# Schematic.net
KiCad netlist of a schematic drawn in EAGLE
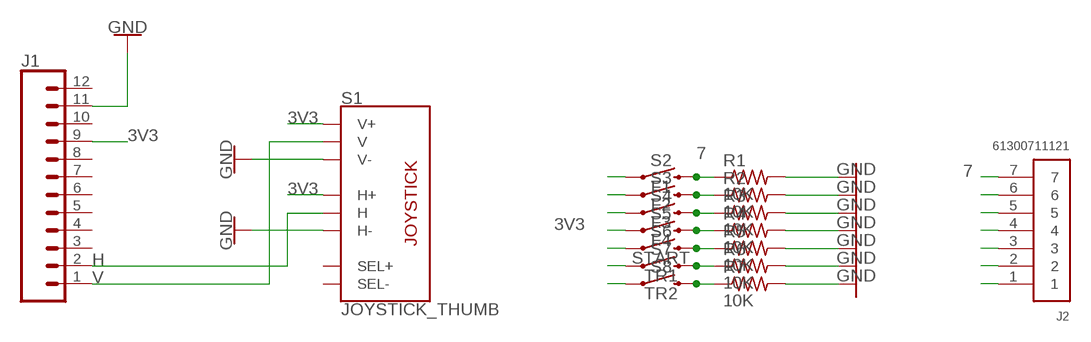
[diagram p0: schematic, sheet 1]

(export (version "E")
  (design (tool "Eeschema 10.0.6"))
  (components
    (comp (ref "J1")
      (value "CONN_12NO_SILK")
      (footprint "eagle-import:1X12_NO_SILK")
      (libsource (lib "eagle-import") (part "CONN_12NO_SILK"))
    )
    (comp (ref "J2")
      (value "61300711121")
      (footprint "eagle-import:61300711121")
      (fields
        (field (name "DIGI_KEY_PART_NUMBER") "732-5320-ND")
        (field (name "MANUFACTURER") "Wurth Electronics Inc.")
        (field (name "CREATED_BY") "PCBLayout.com")
      )
      (libsource (lib "eagle-import") (part "61300711121"))
    )
    (comp (ref "R1")
      (value "10K")
      (footprint "eagle-import:RES_1206")
      (fields
        (field (name "DIGIKEY_PART_NUMBER") "P0.0ETR-ND")
        (field (name "MANUFACTURER") "Panasonic Electronic Components")
        (field (name "MPN") "ERJ-8GEY0R00V")
        (field (name "CREATED_BY") "PCBLayout.com")
      )
      (libsource (lib "eagle-import") (part "ERJ-8GEY0R00V"))
    )
    (comp (ref "R2")
      (value "10K")
      (footprint "eagle-import:RES_1206")
      (fields
        (field (name "DIGIKEY_PART_NUMBER") "P0.0ETR-ND")
        (field (name "MANUFACTURER") "Panasonic Electronic Components")
        (field (name "MPN") "ERJ-8GEY0R00V")
        (field (name "CREATED_BY") "PCBLayout.com")
      )
      (libsource (lib "eagle-import") (part "ERJ-8GEY0R00V"))
    )
    (comp (ref "R3")
      (value "10K")
      (footprint "eagle-import:RES_1206")
      (fields
        (field (name "DIGIKEY_PART_NUMBER") "P0.0ETR-ND")
        (field (name "MANUFACTURER") "Panasonic Electronic Components")
        (field (name "MPN") "ERJ-8GEY0R00V")
        (field (name "CREATED_BY") "PCBLayout.com")
      )
      (libsource (lib "eagle-import") (part "ERJ-8GEY0R00V"))
    )
    (comp (ref "R4")
      (value "10K")
      (footprint "eagle-import:RES_1206")
      (fields
        (field (name "DIGIKEY_PART_NUMBER") "P0.0ETR-ND")
        (field (name "MANUFACTURER") "Panasonic Electronic Components")
        (field (name "MPN") "ERJ-8GEY0R00V")
        (field (name "CREATED_BY") "PCBLayout.com")
      )
      (libsource (lib "eagle-import") (part "ERJ-8GEY0R00V"))
    )
    (comp (ref "R5")
      (value "10K")
      (footprint "eagle-import:RES_1206")
      (fields
        (field (name "DIGIKEY_PART_NUMBER") "P0.0ETR-ND")
        (field (name "MANUFACTURER") "Panasonic Electronic Components")
        (field (name "MPN") "ERJ-8GEY0R00V")
        (field (name "CREATED_BY") "PCBLayout.com")
      )
      (libsource (lib "eagle-import") (part "ERJ-8GEY0R00V"))
    )
    (comp (ref "R6")
      (value "10K")
      (footprint "eagle-import:RES_1206")
      (fields
        (field (name "DIGIKEY_PART_NUMBER") "P0.0ETR-ND")
        (field (name "MANUFACTURER") "Panasonic Electronic Components")
        (field (name "MPN") "ERJ-8GEY0R00V")
        (field (name "CREATED_BY") "PCBLayout.com")
      )
      (libsource (lib "eagle-import") (part "ERJ-8GEY0R00V"))
    )
    (comp (ref "R7")
      (value "10K")
      (footprint "eagle-import:RES_1206")
      (fields
        (field (name "DIGIKEY_PART_NUMBER") "P0.0ETR-ND")
        (field (name "MANUFACTURER") "Panasonic Electronic Components")
        (field (name "MPN") "ERJ-8GEY0R00V")
        (field (name "CREATED_BY") "PCBLayout.com")
      )
      (libsource (lib "eagle-import") (part "ERJ-8GEY0R00V"))
    )
    (comp (ref "S1")
      (value "JOYSTICK_THUMB")
      (footprint "eagle-import:JOYSTICK")
      (libsource (lib "eagle-import") (part "JOYSTICK_THUMB"))
    )
    (comp (ref "S2")
      (value "F1")
      (footprint "eagle-import:TACTILE_SWITCH_PTH_12MM")
      (libsource (lib "eagle-import") (part "MOMENTARY-SWITCH-SPST-PTH-12MM"))
    )
    (comp (ref "S3")
      (value "F2")
      (footprint "eagle-import:TACTILE_SWITCH_PTH_12MM")
      (libsource (lib "eagle-import") (part "MOMENTARY-SWITCH-SPST-PTH-12MM"))
    )
    (comp (ref "S4")
      (value "F3")
      (footprint "eagle-import:TACTILE_SWITCH_PTH_12MM")
      (libsource (lib "eagle-import") (part "MOMENTARY-SWITCH-SPST-PTH-12MM"))
    )
    (comp (ref "S5")
      (value "F4")
      (footprint "eagle-import:TACTILE_SWITCH_PTH_12MM")
      (libsource (lib "eagle-import") (part "MOMENTARY-SWITCH-SPST-PTH-12MM"))
    )
    (comp (ref "S6")
      (value "START")
      (footprint "eagle-import:TACTILE_SWITCH_PTH_12MM")
      (libsource (lib "eagle-import") (part "MOMENTARY-SWITCH-SPST-PTH-12MM"))
    )
    (comp (ref "S7")
      (value "TR1")
      (footprint "eagle-import:TACTILE_SWITCH_PTH_RIGHT_ANGLE_KIT")
      (libsource (lib "eagle-import") (part "MOMENTARY-SWITCH-SPST-PTH-RIGHT-ANGLE-KIT"))
    )
    (comp (ref "S8")
      (value "TR2")
      (footprint "eagle-import:TACTILE_SWITCH_PTH_RIGHT_ANGLE_KIT")
      (libsource (lib "eagle-import") (part "MOMENTARY-SWITCH-SPST-PTH-RIGHT-ANGLE-KIT"))
    )
  )
  (nets
    (net (code "1") (name "/1") (class "Default")
      (node (ref "J2") (pin "1") (pinfunction "1_1") (pintype "passive"))
      (node (ref "R7") (pin "1") (pinfunction "1_1") (pintype "passive"))
      (node (ref "S8") (pin "2") (pinfunction "2_2") (pintype "passive"))
    )
    (net (code "2") (name "/2") (class "Default")
      (node (ref "J2") (pin "2") (pinfunction "2_2") (pintype "passive"))
      (node (ref "R6") (pin "1") (pinfunction "1_1") (pintype "passive"))
      (node (ref "S7") (pin "2") (pinfunction "2_2") (pintype "passive"))
    )
    (net (code "3") (name "/3") (class "Default")
      (node (ref "J2") (pin "3") (pinfunction "3_3") (pintype "passive"))
      (node (ref "R5") (pin "1") (pinfunction "1_1") (pintype "passive"))
      (node (ref "S6") (pin "3") (pinfunction "2_3") (pintype "passive"))
    )
    (net (code "4") (name "/3V3") (class "Default")
      (node (ref "J1") (pin "9") (pinfunction "9_9") (pintype "passive"))
      (node (ref "S1") (pin "H1") (pinfunction "H+_H1") (pintype "bidirectional"))
      (node (ref "S1") (pin "V1") (pinfunction "V+_V1") (pintype "bidirectional"))
      (node (ref "S2") (pin "1") (pinfunction "1_1") (pintype "passive"))
      (node (ref "S3") (pin "1") (pinfunction "1_1") (pintype "passive"))
      (node (ref "S4") (pin "1") (pinfunction "1_1") (pintype "passive"))
      (node (ref "S5") (pin "1") (pinfunction "1_1") (pintype "passive"))
      (node (ref "S6") (pin "1") (pinfunction "1_1") (pintype "passive"))
      (node (ref "S7") (pin "1") (pinfunction "1_1") (pintype "passive"))
      (node (ref "S8") (pin "1") (pinfunction "1_1") (pintype "passive"))
    )
    (net (code "5") (name "/4") (class "Default")
      (node (ref "J2") (pin "4") (pinfunction "4_4") (pintype "passive"))
      (node (ref "R4") (pin "1") (pinfunction "1_1") (pintype "passive"))
      (node (ref "S5") (pin "3") (pinfunction "2_3") (pintype "passive"))
    )
    (net (code "6") (name "/5") (class "Default")
      (node (ref "J2") (pin "5") (pinfunction "5_5") (pintype "passive"))
      (node (ref "R3") (pin "1") (pinfunction "1_1") (pintype "passive"))
      (node (ref "S4") (pin "3") (pinfunction "2_3") (pintype "passive"))
    )
    (net (code "7") (name "/6") (class "Default")
      (node (ref "J2") (pin "6") (pinfunction "6_6") (pintype "passive"))
      (node (ref "R2") (pin "1") (pinfunction "1_1") (pintype "passive"))
      (node (ref "S3") (pin "3") (pinfunction "2_3") (pintype "passive"))
    )
    (net (code "8") (name "/7") (class "Default")
      (node (ref "J2") (pin "7") (pinfunction "7_7") (pintype "passive"))
      (node (ref "R1") (pin "1") (pinfunction "1_1") (pintype "passive"))
      (node (ref "S2") (pin "3") (pinfunction "2_3") (pintype "passive"))
    )
    (net (code "9") (name "/H") (class "Default")
      (node (ref "J1") (pin "2") (pinfunction "2_2") (pintype "passive"))
      (node (ref "S1") (pin "H2") (pinfunction "H_H2") (pintype "bidirectional"))
    )
    (net (code "10") (name "/V") (class "Default")
      (node (ref "J1") (pin "1") (pinfunction "1_1") (pintype "passive"))
      (node (ref "S1") (pin "V2") (pinfunction "V_V2") (pintype "bidirectional"))
    )
    (net (code "11") (name "GND") (class "Default")
      (node (ref "J1") (pin "11") (pinfunction "11_11") (pintype "passive"))
      (node (ref "R1") (pin "2") (pinfunction "2_2") (pintype "passive"))
      (node (ref "R2") (pin "2") (pinfunction "2_2") (pintype "passive"))
      (node (ref "R3") (pin "2") (pinfunction "2_2") (pintype "passive"))
      (node (ref "R4") (pin "2") (pinfunction "2_2") (pintype "passive"))
      (node (ref "R5") (pin "2") (pinfunction "2_2") (pintype "passive"))
      (node (ref "R6") (pin "2") (pinfunction "2_2") (pintype "passive"))
      (node (ref "R7") (pin "2") (pinfunction "2_2") (pintype "passive"))
      (node (ref "S1") (pin "H3") (pinfunction "H-_H3") (pintype "bidirectional"))
      (node (ref "S1") (pin "V3") (pinfunction "V-_V3") (pintype "bidirectional"))
    )
    (net (code "12") (name "unconnected-(J1-Pad3)") (class "Default")
      (node (ref "J1") (pin "3") (pinfunction "3_3") (pintype "passive"))
    )
    (net (code "13") (name "unconnected-(J1-Pad4)") (class "Default")
      (node (ref "J1") (pin "4") (pinfunction "4_4") (pintype "passive"))
    )
    (net (code "14") (name "unconnected-(J1-Pad5)") (class "Default")
      (node (ref "J1") (pin "5") (pinfunction "5_5") (pintype "passive"))
    )
    (net (code "15") (name "unconnected-(J1-Pad6)") (class "Default")
      (node (ref "J1") (pin "6") (pinfunction "6_6") (pintype "passive"))
    )
    (net (code "16") (name "unconnected-(J1-Pad7)") (class "Default")
      (node (ref "J1") (pin "7") (pinfunction "7_7") (pintype "passive"))
    )
    (net (code "17") (name "unconnected-(J1-Pad8)") (class "Default")
      (node (ref "J1") (pin "8") (pinfunction "8_8") (pintype "passive"))
    )
    (net (code "18") (name "unconnected-(J1-Pad10)") (class "Default")
      (node (ref "J1") (pin "10") (pinfunction "10_10") (pintype "passive"))
    )
    (net (code "19") (name "unconnected-(J1-Pad12)") (class "Default")
      (node (ref "J1") (pin "12") (pinfunction "12_12") (pintype "passive"))
    )
    (net (code "20") (name "unconnected-(S1-SEL+-PadB1A)") (class "Default")
      (node (ref "S1") (pin "B1A") (pinfunction "SEL+_B1A") (pintype "bidirectional"))
    )
    (net (code "21") (name "unconnected-(S1-SEL--PadB2A)") (class "Default")
      (node (ref "S1") (pin "B2A") (pinfunction "SEL-_B2A") (pintype "bidirectional"))
    )
  )
)
